# sd_card.net
KiCad netlist of a schematic drawn in Altium Designer
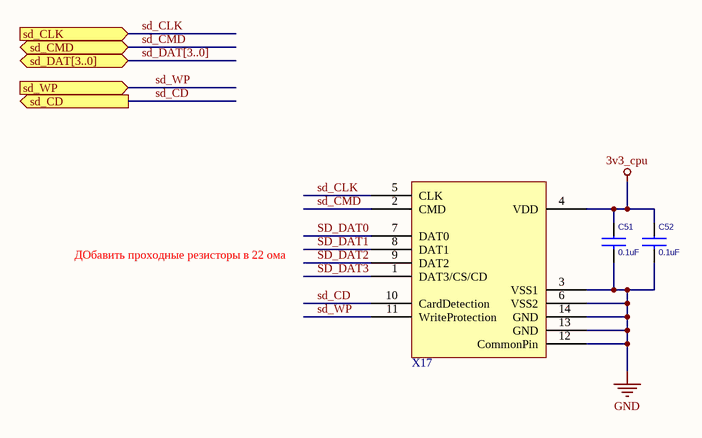
[diagram p0: sd_card.SchDoc]

(export (version "E")
  (design (tool "Eeschema 10.0.6"))
  (components
    (comp (ref "C51")
      (value "0.1uF")
      (footprint "CAPC2012X09M")
      (description "CAP CER 0.1UF 25V 10% X7R 0805")
      (libsource (lib "Capacitors") (part "CAP_SMD_0.1UF_10%"))
    )
    (comp (ref "C52")
      (value "0.1uF")
      (footprint "CAPC2012X09M")
      (description "CAP CER 0.1UF 25V 10% X7R 0805")
      (libsource (lib "Capacitors") (part "CAP_SMD_0.1UF_10%"))
    )
    (comp (ref "X17")
      (value "104H-TDA0-R01")
      (footprint "104H-TDA0-R01")
      (libsource (lib "Connectors") (part "104H-TDA0-R01"))
    )
  )
  (nets
    (net (code "5") (name "/SD_DAT0") (class "Default")
      (node (ref "X17") (pin "7") (pinfunction "DAT0_7") (pintype "power_in"))
    )
    (net (code "6") (name "/SD_DAT1") (class "Default")
      (node (ref "X17") (pin "8") (pinfunction "DAT1_8") (pintype "power_in"))
    )
    (net (code "7") (name "/SD_DAT2") (class "Default")
      (node (ref "X17") (pin "9") (pinfunction "DAT2_9") (pintype "power_in"))
    )
    (net (code "8") (name "/SD_DAT3") (class "Default")
      (node (ref "X17") (pin "1") (pinfunction "DAT3/CS/CD_1") (pintype "power_in"))
    )
    (net (code "9") (name "/sd_CD") (class "Default")
      (node (ref "X17") (pin "10") (pinfunction "CardDetection_10") (pintype "power_in"))
    )
    (net (code "10") (name "/sd_CLK") (class "Default")
      (node (ref "X17") (pin "5") (pinfunction "CLK_5") (pintype "power_in"))
    )
    (net (code "11") (name "/sd_CMD") (class "Default")
      (node (ref "X17") (pin "2") (pinfunction "CMD_2") (pintype "power_in"))
    )
    (net (code "13") (name "/sd_WP") (class "Default")
      (node (ref "X17") (pin "11") (pinfunction "WriteProtection_11") (pintype "power_in"))
    )
    (net (code "14") (name "3v3_cpu") (class "Default")
      (node (ref "C51") (pin "1") (pinfunction "1_1") (pintype "passive"))
      (node (ref "C52") (pin "1") (pinfunction "1_1") (pintype "passive"))
      (node (ref "X17") (pin "4") (pinfunction "VDD_4") (pintype "power_in"))
    )
    (net (code "15") (name "GND") (class "Default")
      (node (ref "C51") (pin "2") (pinfunction "2_2") (pintype "passive"))
      (node (ref "C52") (pin "2") (pinfunction "2_2") (pintype "passive"))
      (node (ref "X17") (pin "12") (pinfunction "CommonPin_12") (pintype "power_in"))
      (node (ref "X17") (pin "13") (pinfunction "GND_13") (pintype "power_in"))
      (node (ref "X17") (pin "14") (pinfunction "GND_14") (pintype "power_in"))
      (node (ref "X17") (pin "3") (pinfunction "VSS1_3") (pintype "power_in"))
      (node (ref "X17") (pin "6") (pinfunction "VSS2_6") (pintype "power_in"))
    )
  )
)
